# GR_Architecture.net
KiCad netlist of a schematic drawn in Altium Designer
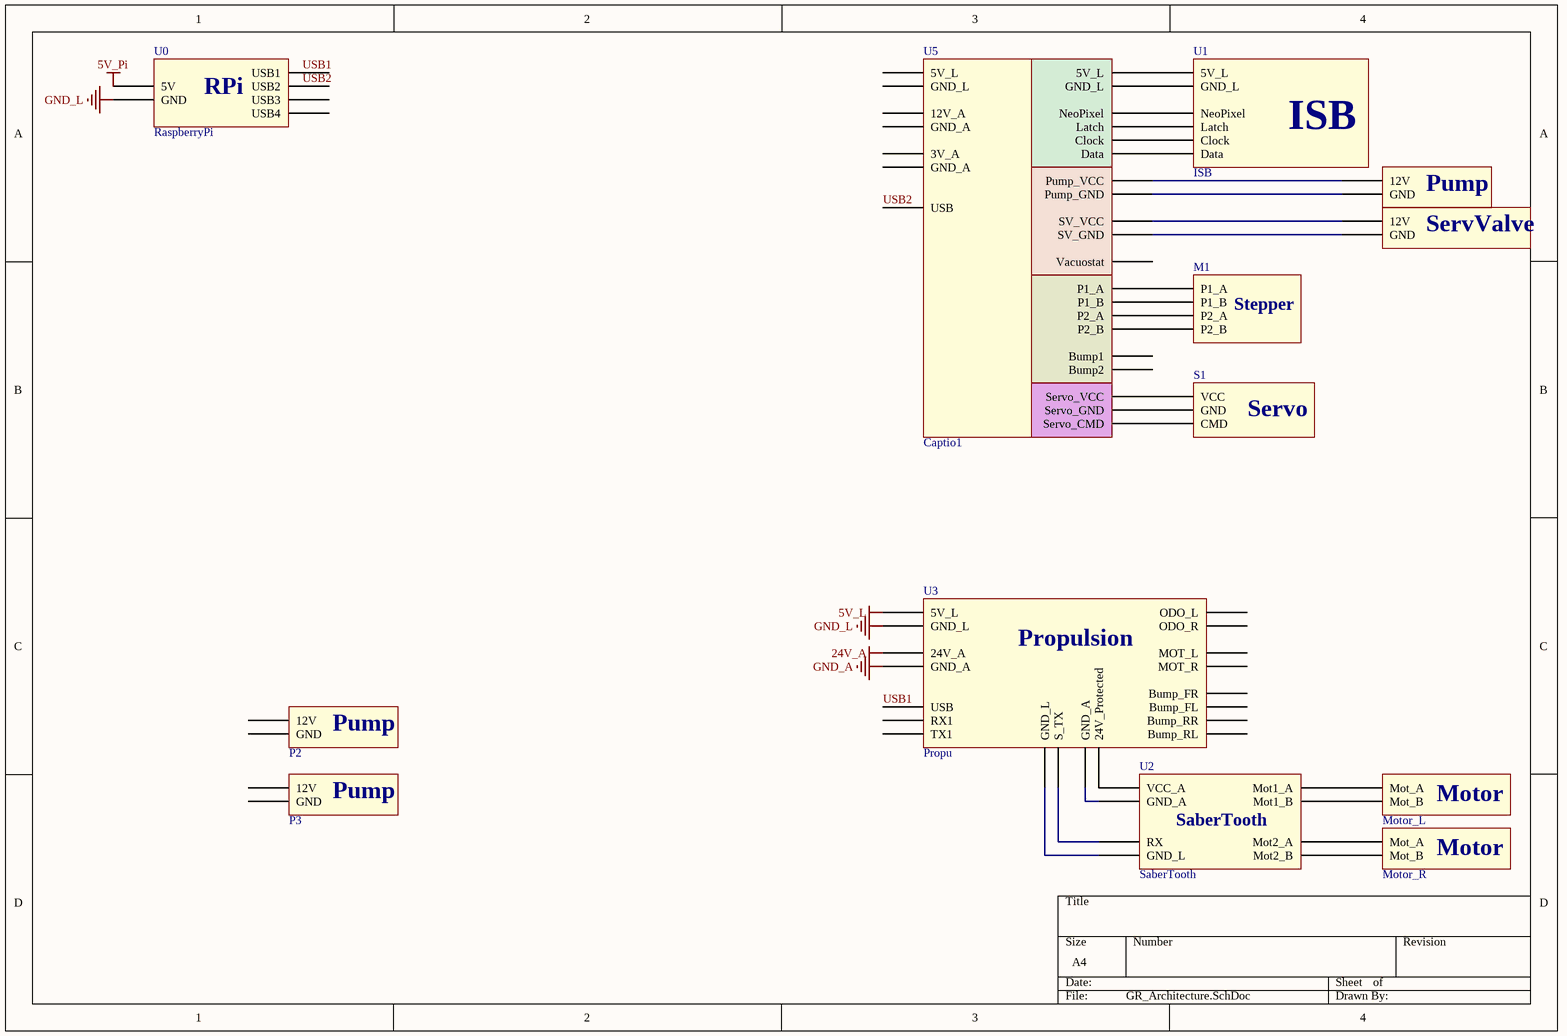
[diagram p0: GR_Architecture.SchDoc]

(export (version "E")
  (design (tool "Eeschema 10.0.6"))
  (components
    (comp (ref "M1") (value "Stepper") (libsource (lib "Cards") (part "Stepper")))
    (comp (ref "Motor_L") (value "Motor") (libsource (lib "Cards") (part "Motor")))
    (comp (ref "Motor_R") (value "Motor") (libsource (lib "Cards") (part "Motor")))
    (comp (ref "P1") (value "Pump") (libsource (lib "Cards") (part "Pump")))
    (comp (ref "P2") (value "Pump") (libsource (lib "Cards") (part "Pump")))
    (comp (ref "P3") (value "Pump") (libsource (lib "Cards") (part "Pump")))
    (comp (ref "S1") (value "Servo") (libsource (lib "Cards") (part "Servo")))
    (comp (ref "Se1") (value "ServoValve") (libsource (lib "Cards") (part "ServoValve")))
    (comp (ref "U0") (value "RaspberryPi") (libsource (lib "Cards") (part "RaspberryPi")))
    (comp (ref "U1") (value "ISB") (libsource (lib "Cards") (part "ISB")))
    (comp (ref "U2") (value "SaberTooth") (libsource (lib "Cards") (part "SaberTooth")))
    (comp (ref "U3") (value "Propu") (libsource (lib "Cards") (part "Propu")))
    (comp (ref "U5") (value "Captio1") (libsource (lib "Cards") (part "Captio1")))
  )
  (nets
    (net (code "1") (name "/USB1") (class "Default")
      (node (ref "U3") (pin "47") (pinfunction "USB_47") (pintype "passive"))
    )
    (net (code "2") (name "/USB2") (class "Default")
      (node (ref "U5") (pin "82") (pinfunction "USB_82") (pintype "passive"))
    )
    (net (code "3") (name "5V_L") (class "Default")
      (node (ref "U3") (pin "43") (pinfunction "5V_L_43") (pintype "passive"))
    )
    (net (code "4") (name "5V_Pi") (class "Default")
      (node (ref "U0") (pin "74") (pinfunction "5V_74") (pintype "passive"))
    )
    (net (code "5") (name "24V_A") (class "Default")
      (node (ref "U3") (pin "45") (pinfunction "24V_A_45") (pintype "passive"))
    )
    (net (code "6") (name "GND_A") (class "Default")
      (node (ref "U3") (pin "46") (pinfunction "GND_A_46") (pintype "passive"))
    )
    (net (code "7") (name "GND_L") (class "Default")
      (node (ref "U0") (pin "75") (pinfunction "GND_75") (pintype "passive"))
      (node (ref "U3") (pin "44") (pinfunction "GND_L_44") (pintype "passive"))
    )
    (net (code "8") (name "Net-(M1-P1_A)") (class "Default")
      (node (ref "M1") (pin "87") (pinfunction "P1_A_87") (pintype "passive"))
      (node (ref "U5") (pin "83") (pinfunction "P1_A_83") (pintype "passive"))
    )
    (net (code "9") (name "Net-(M1-P1_B)") (class "Default")
      (node (ref "M1") (pin "88") (pinfunction "P1_B_88") (pintype "passive"))
      (node (ref "U5") (pin "84") (pinfunction "P1_B_84") (pintype "passive"))
    )
    (net (code "10") (name "Net-(M1-P2_A)") (class "Default")
      (node (ref "M1") (pin "89") (pinfunction "P2_A_89") (pintype "passive"))
      (node (ref "U5") (pin "85") (pinfunction "P2_A_85") (pintype "passive"))
    )
    (net (code "11") (name "Net-(M1-P2_B)") (class "Default")
      (node (ref "M1") (pin "90") (pinfunction "P2_B_90") (pintype "passive"))
      (node (ref "U5") (pin "86") (pinfunction "P2_B_86") (pintype "passive"))
    )
    (net (code "12") (name "Net-(Motor_L-Mot_A)") (class "Default")
      (node (ref "Motor_L") (pin "65") (pinfunction "Mot_A_65") (pintype "passive"))
      (node (ref "U2") (pin "70") (pinfunction "Mot1_A_70") (pintype "passive"))
    )
    (net (code "13") (name "Net-(Motor_L-Mot_B)") (class "Default")
      (node (ref "Motor_L") (pin "64") (pinfunction "Mot_B_64") (pintype "passive"))
      (node (ref "U2") (pin "71") (pinfunction "Mot1_B_71") (pintype "passive"))
    )
    (net (code "14") (name "Net-(Motor_R-Mot_A)") (class "Default")
      (node (ref "Motor_R") (pin "65") (pinfunction "Mot_A_65") (pintype "passive"))
      (node (ref "U2") (pin "72") (pinfunction "Mot2_A_72") (pintype "passive"))
    )
    (net (code "15") (name "Net-(Motor_R-Mot_B)") (class "Default")
      (node (ref "Motor_R") (pin "64") (pinfunction "Mot_B_64") (pintype "passive"))
      (node (ref "U2") (pin "73") (pinfunction "Mot2_B_73") (pintype "passive"))
    )
    (net (code "16") (name "Net-(P1-12V)") (class "Default")
      (node (ref "P1") (pin "41") (pinfunction "12V_41") (pintype "passive"))
      (node (ref "U5") (pin "83") (pinfunction "Pump_VCC_83") (pintype "passive"))
    )
    (net (code "17") (name "Net-(P1-GND)") (class "Default")
      (node (ref "P1") (pin "42") (pinfunction "GND_42") (pintype "passive"))
      (node (ref "U5") (pin "84") (pinfunction "Pump_GND_84") (pintype "passive"))
    )
    (net (code "18") (name "Net-(S1-CMD)") (class "Default")
      (node (ref "S1") (pin "93") (pinfunction "CMD_93") (pintype "passive"))
      (node (ref "U5") (pin "86") (pinfunction "Servo_CMD_86") (pintype "passive"))
    )
    (net (code "19") (name "Net-(S1-GND)") (class "Default")
      (node (ref "S1") (pin "92") (pinfunction "GND_92") (pintype "passive"))
      (node (ref "U5") (pin "86") (pinfunction "Servo_GND_86") (pintype "passive"))
    )
    (net (code "20") (name "Net-(S1-VCC)") (class "Default")
      (node (ref "S1") (pin "91") (pinfunction "VCC_91") (pintype "passive"))
      (node (ref "U5") (pin "86") (pinfunction "Servo_VCC_86") (pintype "passive"))
    )
    (net (code "21") (name "Net-(Se1-12V)") (class "Default")
      (node (ref "Se1") (pin "41") (pinfunction "12V_41") (pintype "passive"))
      (node (ref "U5") (pin "85") (pinfunction "SV_VCC_85") (pintype "passive"))
    )
    (net (code "22") (name "Net-(Se1-GND)") (class "Default")
      (node (ref "Se1") (pin "42") (pinfunction "GND_42") (pintype "passive"))
      (node (ref "U5") (pin "86") (pinfunction "SV_GND_86") (pintype "passive"))
    )
    (net (code "23") (name "Net-(U1-5V_L)") (class "Default")
      (node (ref "U1") (pin "35") (pinfunction "5V_L_35") (pintype "passive"))
      (node (ref "U5") (pin "35") (pinfunction "5V_L_35") (pintype "passive"))
    )
    (net (code "24") (name "Net-(U1-Clock)") (class "Default")
      (node (ref "U1") (pin "39") (pinfunction "Clock_39") (pintype "passive"))
      (node (ref "U5") (pin "39") (pinfunction "Clock_39") (pintype "passive"))
    )
    (net (code "25") (name "Net-(U1-Data)") (class "Default")
      (node (ref "U1") (pin "40") (pinfunction "Data_40") (pintype "passive"))
      (node (ref "U5") (pin "40") (pinfunction "Data_40") (pintype "passive"))
    )
    (net (code "26") (name "Net-(U1-GND_L)") (class "Default")
      (node (ref "U1") (pin "36") (pinfunction "GND_L_36") (pintype "passive"))
      (node (ref "U5") (pin "36") (pinfunction "GND_L_36") (pintype "passive"))
    )
    (net (code "27") (name "Net-(U1-Latch)") (class "Default")
      (node (ref "U1") (pin "38") (pinfunction "Latch_38") (pintype "passive"))
      (node (ref "U5") (pin "38") (pinfunction "Latch_38") (pintype "passive"))
    )
    (net (code "28") (name "Net-(U1-NeoPixel)") (class "Default")
      (node (ref "U1") (pin "37") (pinfunction "NeoPixel_37") (pintype "passive"))
      (node (ref "U5") (pin "37") (pinfunction "NeoPixel_37") (pintype "passive"))
    )
    (net (code "29") (name "Net-(U2-GND_A)") (class "Default")
      (node (ref "U2") (pin "67") (pinfunction "GND_A_67") (pintype "passive"))
      (node (ref "U3") (pin "50") (pinfunction "GND_A_50") (pintype "passive"))
    )
    (net (code "30") (name "Net-(U2-GND_L)") (class "Default")
      (node (ref "U2") (pin "69") (pinfunction "GND_L_69") (pintype "passive"))
      (node (ref "U3") (pin "53") (pinfunction "GND_L_53") (pintype "passive"))
    )
    (net (code "31") (name "Net-(U2-RX)") (class "Default")
      (node (ref "U2") (pin "68") (pinfunction "RX_68") (pintype "passive"))
      (node (ref "U3") (pin "52") (pinfunction "S_TX_52") (pintype "passive"))
    )
    (net (code "32") (name "Net-(U2-VCC_A)") (class "Default")
      (node (ref "U2") (pin "66") (pinfunction "VCC_A_66") (pintype "passive"))
      (node (ref "U3") (pin "49") (pinfunction "24V_Protected_49") (pintype "passive"))
    )
    (net (code "33") (name "unconnected-(P2-12V-Pad41)") (class "Default")
      (node (ref "P2") (pin "41") (pinfunction "12V_41") (pintype "passive"))
    )
    (net (code "34") (name "unconnected-(P2-GND-Pad42)") (class "Default")
      (node (ref "P2") (pin "42") (pinfunction "GND_42") (pintype "passive"))
    )
    (net (code "35") (name "unconnected-(P3-12V-Pad41)") (class "Default")
      (node (ref "P3") (pin "41") (pinfunction "12V_41") (pintype "passive"))
    )
    (net (code "36") (name "unconnected-(P3-GND-Pad42)") (class "Default")
      (node (ref "P3") (pin "42") (pinfunction "GND_42") (pintype "passive"))
    )
    (net (code "37") (name "unconnected-(U0-USB1-Pad76)") (class "Default")
      (node (ref "U0") (pin "76") (pinfunction "USB1_76") (pintype "passive"))
    )
    (net (code "38") (name "unconnected-(U0-USB2-Pad77)") (class "Default")
      (node (ref "U0") (pin "77") (pinfunction "USB2_77") (pintype "passive"))
    )
    (net (code "39") (name "unconnected-(U0-USB3-Pad78)") (class "Default")
      (node (ref "U0") (pin "78") (pinfunction "USB3_78") (pintype "passive"))
    )
    (net (code "40") (name "unconnected-(U0-USB4-Pad79)") (class "Default")
      (node (ref "U0") (pin "79") (pinfunction "USB4_79") (pintype "passive"))
    )
    (net (code "41") (name "unconnected-(U3-Bump_FL-Pad59)") (class "Default")
      (node (ref "U3") (pin "59") (pinfunction "Bump_FL_59") (pintype "passive"))
    )
    (net (code "42") (name "unconnected-(U3-Bump_FR-Pad58)") (class "Default")
      (node (ref "U3") (pin "58") (pinfunction "Bump_FR_58") (pintype "passive"))
    )
    (net (code "43") (name "unconnected-(U3-Bump_RL-Pad63)") (class "Default")
      (node (ref "U3") (pin "63") (pinfunction "Bump_RL_63") (pintype "passive"))
    )
    (net (code "44") (name "unconnected-(U3-Bump_RR-Pad62)") (class "Default")
      (node (ref "U3") (pin "62") (pinfunction "Bump_RR_62") (pintype "passive"))
    )
    (net (code "45") (name "unconnected-(U3-MOT_L-Pad56)") (class "Default")
      (node (ref "U3") (pin "56") (pinfunction "MOT_L_56") (pintype "passive"))
    )
    (net (code "46") (name "unconnected-(U3-MOT_R-Pad57)") (class "Default")
      (node (ref "U3") (pin "57") (pinfunction "MOT_R_57") (pintype "passive"))
    )
    (net (code "47") (name "unconnected-(U3-ODO_L-Pad54)") (class "Default")
      (node (ref "U3") (pin "54") (pinfunction "ODO_L_54") (pintype "passive"))
    )
    (net (code "48") (name "unconnected-(U3-ODO_R-Pad55)") (class "Default")
      (node (ref "U3") (pin "55") (pinfunction "ODO_R_55") (pintype "passive"))
    )
    (net (code "49") (name "unconnected-(U3-RX1-Pad60)") (class "Default")
      (node (ref "U3") (pin "60") (pinfunction "RX1_60") (pintype "passive"))
    )
    (net (code "50") (name "unconnected-(U3-TX1-Pad61)") (class "Default")
      (node (ref "U3") (pin "61") (pinfunction "TX1_61") (pintype "passive"))
    )
    (net (code "51") (name "unconnected-(U5-3V_A-Pad80)") (class "Default")
      (node (ref "U5") (pin "80") (pinfunction "3V_A_80") (pintype "passive"))
    )
    (net (code "52") (name "unconnected-(U5-5V_L-Pad80)") (class "Default")
      (node (ref "U5") (pin "80") (pinfunction "5V_L_80") (pintype "passive"))
    )
    (net (code "53") (name "unconnected-(U5-12V_A-Pad80)") (class "Default")
      (node (ref "U5") (pin "80") (pinfunction "12V_A_80") (pintype "passive"))
    )
    (net (code "54") (name "unconnected-(U5-Bump1-Pad86)") (class "Default")
      (node (ref "U5") (pin "86") (pinfunction "Bump1_86") (pintype "passive"))
    )
    (net (code "55") (name "unconnected-(U5-Bump2-Pad86)") (class "Default")
      (node (ref "U5") (pin "86") (pinfunction "Bump2_86") (pintype "passive"))
    )
    (net (code "56") (name "unconnected-(U5-GND_A-Pad81)") (class "Default")
      (node (ref "U5") (pin "81") (pinfunction "GND_A_81") (pintype "passive"))
    )
    (net (code "57") (name "unconnected-(U5-GND_A-Pad81)_1") (class "Default")
      (node (ref "U5") (pin "81") (pinfunction "GND_A_81") (pintype "passive"))
    )
    (net (code "58") (name "unconnected-(U5-GND_L-Pad81)") (class "Default")
      (node (ref "U5") (pin "81") (pinfunction "GND_L_81") (pintype "passive"))
    )
    (net (code "59") (name "unconnected-(U5-Vacuostat-Pad86)") (class "Default")
      (node (ref "U5") (pin "86") (pinfunction "Vacuostat_86") (pintype "passive"))
    )
  )
)
